# PCB_PUMP_LED.net
KiCad netlist of a schematic drawn in EAGLE
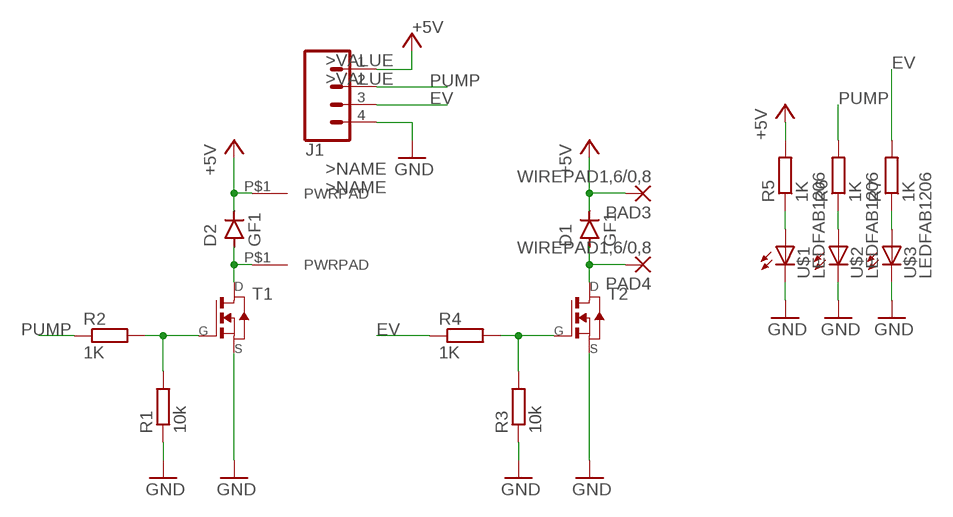
[diagram p0: schematic, sheet 1]

(export (version "E")
  (design (tool "Eeschema 10.0.6"))
  (components
    (comp (ref "D1")
      (value "GF1")
      (footprint "eagle-import:SMA-DO214AC")
      (libsource (lib "eagle-import") (part "GF1"))
    )
    (comp (ref "D2")
      (value "GF1")
      (footprint "eagle-import:SMA-DO214AC")
      (libsource (lib "eagle-import") (part "GF1"))
    )
    (comp (ref "J1")
      (value "CONN_04POLAR")
      (footprint "eagle-import:MOLEX-1X4")
      (libsource (lib "eagle-import") (part "CONN_04POLAR"))
    )
    (comp (ref "J3")
      (value "PWRPAD2-5MM")
      (footprint "eagle-import:PWRPAD_2-5MM")
      (libsource (lib "eagle-import") (part "PWRPAD2-5MM"))
    )
    (comp (ref "J4")
      (value "PWRPAD2-5MM")
      (footprint "eagle-import:PWRPAD_2-5MM")
      (libsource (lib "eagle-import") (part "PWRPAD2-5MM"))
    )
    (comp (ref "PAD3")
      (value "WIREPAD1,6/0,8")
      (footprint "eagle-import:1,6_0,8")
      (libsource (lib "eagle-import") (part "WIREPAD1,6/0,8"))
    )
    (comp (ref "PAD4")
      (value "WIREPAD1,6/0,8")
      (footprint "eagle-import:1,6_0,8")
      (libsource (lib "eagle-import") (part "WIREPAD1,6/0,8"))
    )
    (comp (ref "R1")
      (value "10k")
      (footprint "eagle-import:R1206")
      (libsource (lib "eagle-import") (part "R-EU_R1206"))
    )
    (comp (ref "R2")
      (value "1K")
      (footprint "eagle-import:R1206")
      (libsource (lib "eagle-import") (part "R-EU_R1206"))
    )
    (comp (ref "R3")
      (value "10k")
      (footprint "eagle-import:R1206")
      (libsource (lib "eagle-import") (part "R-EU_R1206"))
    )
    (comp (ref "R4")
      (value "1K")
      (footprint "eagle-import:R1206")
      (libsource (lib "eagle-import") (part "R-EU_R1206"))
    )
    (comp (ref "R5")
      (value "1K")
      (footprint "eagle-import:R1206")
      (libsource (lib "eagle-import") (part "R-EU_R1206"))
    )
    (comp (ref "R6")
      (value "1K")
      (footprint "eagle-import:R1206")
      (libsource (lib "eagle-import") (part "R-EU_R1206"))
    )
    (comp (ref "R7")
      (value "1K")
      (footprint "eagle-import:R1206")
      (libsource (lib "eagle-import") (part "R-EU_R1206"))
    )
    (comp (ref "T1")
      (value "NMOSFETSOT23")
      (footprint "eagle-import:SOT-23")
      (libsource (lib "eagle-import") (part "NMOSFETSOT23"))
    )
    (comp (ref "T2")
      (value "NMOSFETSOT23")
      (footprint "eagle-import:SOT-23")
      (libsource (lib "eagle-import") (part "NMOSFETSOT23"))
    )
    (comp (ref "U$1")
      (value "LEDFAB1206")
      (footprint "eagle-import:LED1206FAB")
      (libsource (lib "eagle-import") (part "LEDFAB1206"))
    )
    (comp (ref "U$2")
      (value "LEDFAB1206")
      (footprint "eagle-import:LED1206FAB")
      (libsource (lib "eagle-import") (part "LEDFAB1206"))
    )
    (comp (ref "U$3")
      (value "LEDFAB1206")
      (footprint "eagle-import:LED1206FAB")
      (libsource (lib "eagle-import") (part "LEDFAB1206"))
    )
  )
  (nets
    (net (code "1") (name "+5V") (class "Default")
      (node (ref "D1") (pin "K") (pinfunction "C_K") (pintype "passive"))
      (node (ref "D2") (pin "K") (pinfunction "C_K") (pintype "passive"))
      (node (ref "J1") (pin "1") (pinfunction "1_1") (pintype "passive"))
      (node (ref "J4") (pin "P$1") (pinfunction "PWRPAD_P$1") (pintype "bidirectional"))
      (node (ref "PAD3") (pin "1") (pinfunction "P_1") (pintype "passive"))
      (node (ref "R5") (pin "2") (pinfunction "2_2") (pintype "passive"))
    )
    (net (code "2") (name "/EV") (class "Default")
      (node (ref "J1") (pin "3") (pinfunction "3_3") (pintype "passive"))
      (node (ref "R4") (pin "1") (pinfunction "1_1") (pintype "passive"))
      (node (ref "R7") (pin "2") (pinfunction "2_2") (pintype "passive"))
    )
    (net (code "3") (name "/PUMP") (class "Default")
      (node (ref "J1") (pin "2") (pinfunction "2_2") (pintype "passive"))
      (node (ref "R2") (pin "1") (pinfunction "1_1") (pintype "passive"))
      (node (ref "R6") (pin "2") (pinfunction "2_2") (pintype "passive"))
    )
    (net (code "4") (name "GND") (class "Default")
      (node (ref "J1") (pin "4") (pinfunction "4_4") (pintype "passive"))
      (node (ref "R1") (pin "1") (pinfunction "1_1") (pintype "passive"))
      (node (ref "R3") (pin "1") (pinfunction "1_1") (pintype "passive"))
      (node (ref "T1") (pin "2") (pinfunction "S_2") (pintype "passive"))
      (node (ref "T2") (pin "2") (pinfunction "S_2") (pintype "passive"))
      (node (ref "U$1") (pin "2") (pinfunction "C_2") (pintype "passive"))
      (node (ref "U$2") (pin "2") (pinfunction "C_2") (pintype "passive"))
      (node (ref "U$3") (pin "2") (pinfunction "C_2") (pintype "passive"))
    )
    (net (code "5") (name "Net-(J3-PWRPAD)") (class "Default")
      (node (ref "D2") (pin "A") (pinfunction "A_A") (pintype "passive"))
      (node (ref "J3") (pin "P$1") (pinfunction "PWRPAD_P$1") (pintype "bidirectional"))
      (node (ref "T1") (pin "1") (pinfunction "D_1") (pintype "passive"))
    )
    (net (code "6") (name "Net-(PAD4-P)") (class "Default")
      (node (ref "D1") (pin "A") (pinfunction "A_A") (pintype "passive"))
      (node (ref "PAD4") (pin "1") (pinfunction "P_1") (pintype "passive"))
      (node (ref "T2") (pin "1") (pinfunction "D_1") (pintype "passive"))
    )
    (net (code "7") (name "Net-(T1-G)") (class "Default")
      (node (ref "R1") (pin "2") (pinfunction "2_2") (pintype "passive"))
      (node (ref "R2") (pin "2") (pinfunction "2_2") (pintype "passive"))
      (node (ref "T1") (pin "3") (pinfunction "G_3") (pintype "passive"))
    )
    (net (code "8") (name "Net-(T2-G)") (class "Default")
      (node (ref "R3") (pin "2") (pinfunction "2_2") (pintype "passive"))
      (node (ref "R4") (pin "2") (pinfunction "2_2") (pintype "passive"))
      (node (ref "T2") (pin "3") (pinfunction "G_3") (pintype "passive"))
    )
    (net (code "9") (name "Net-(U$1-A)") (class "Default")
      (node (ref "R5") (pin "1") (pinfunction "1_1") (pintype "passive"))
      (node (ref "U$1") (pin "1") (pinfunction "A_1") (pintype "passive"))
    )
    (net (code "10") (name "Net-(U$2-A)") (class "Default")
      (node (ref "R6") (pin "1") (pinfunction "1_1") (pintype "passive"))
      (node (ref "U$2") (pin "1") (pinfunction "A_1") (pintype "passive"))
    )
    (net (code "11") (name "Net-(U$3-A)") (class "Default")
      (node (ref "R7") (pin "1") (pinfunction "1_1") (pintype "passive"))
      (node (ref "U$3") (pin "1") (pinfunction "A_1") (pintype "passive"))
    )
  )
)
